# SFX100_LeonardoBreakout.net
KiCad netlist of a schematic drawn in EAGLE
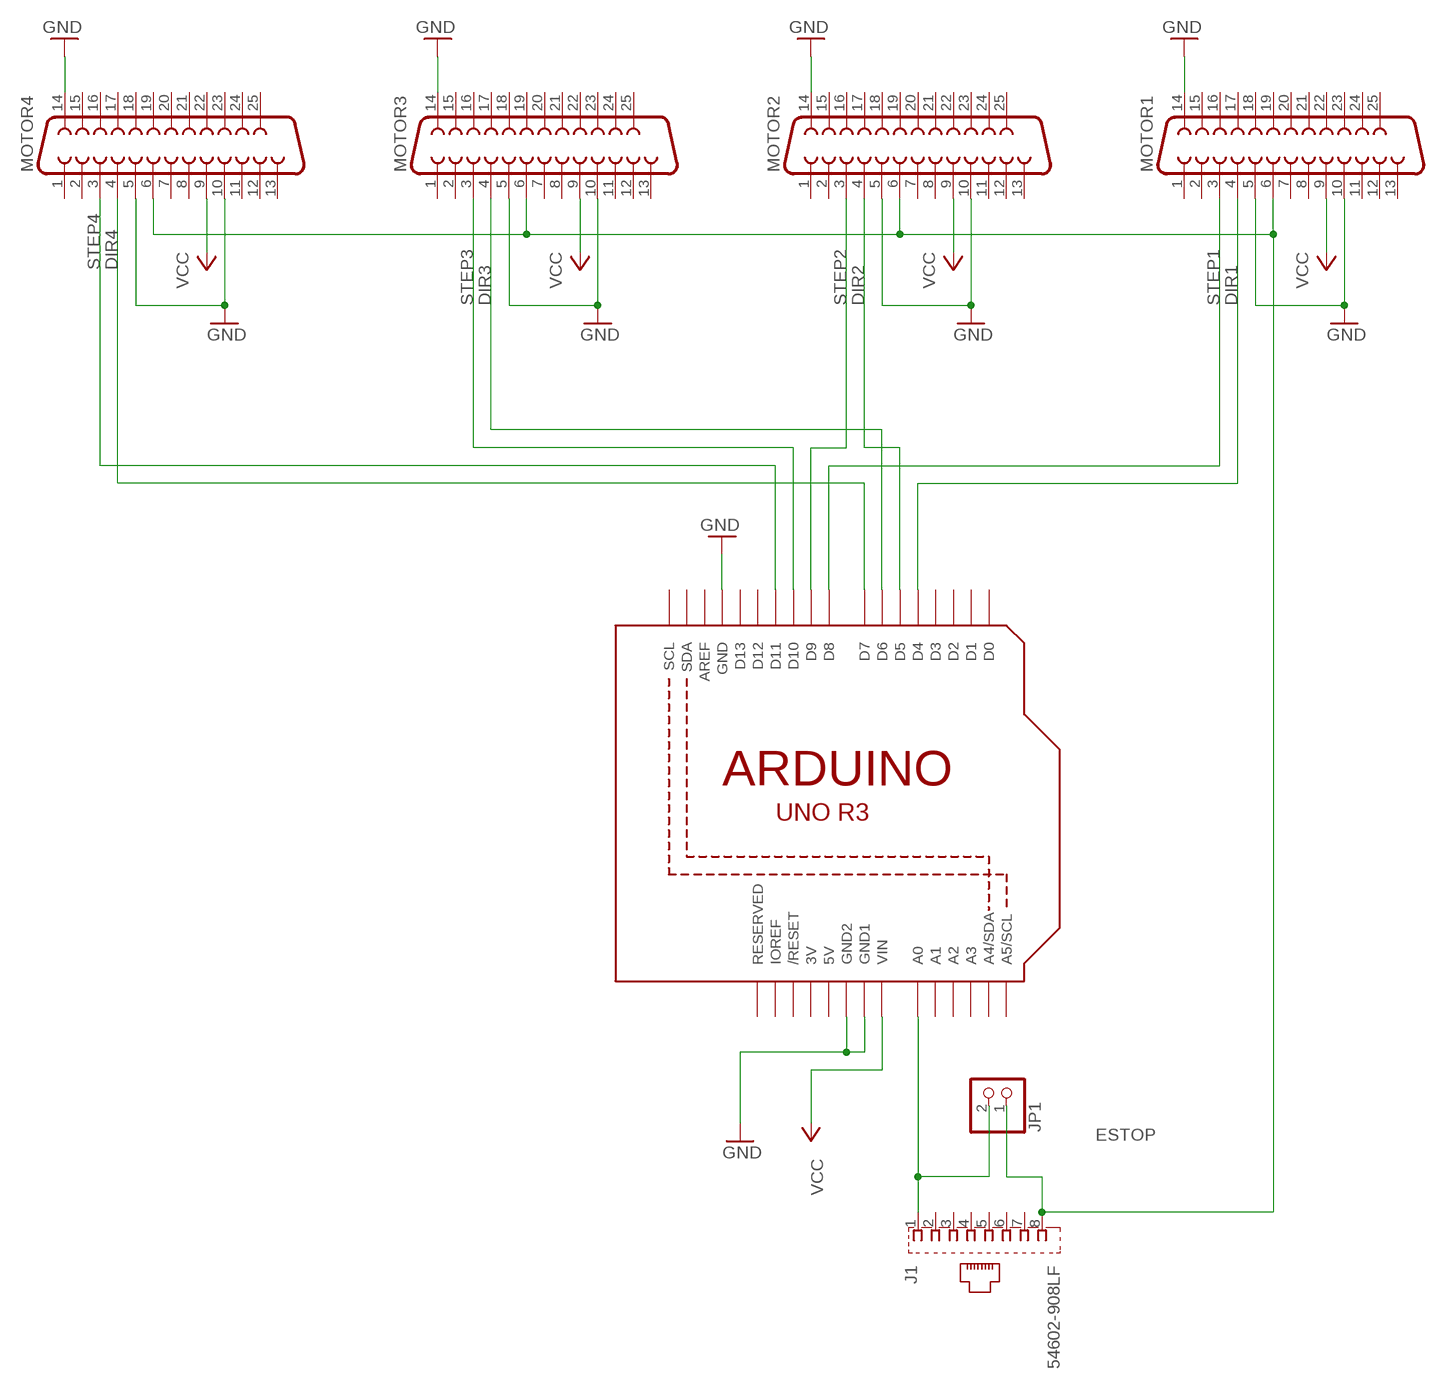
[diagram p0: schematic, sheet 1]

(export (version "E")
  (design (tool "Eeschema 10.0.6"))
  (components
    (comp (ref "J1")
      (value "54602-908LF")
      (footprint "eagle-import:AMPHENOL_54602-908LF")
      (fields (field (name "DIGI-KEY_PART_NUMBER") "609-1046-ND") (field (name "MF") "Amphenol ICC"))
      (libsource (lib "eagle-import") (part "54602-908LF"))
    )
    (comp (ref "JP1")
      (value "PINHD-1X2")
      (footprint "eagle-import:1X02")
      (libsource (lib "eagle-import") (part "PINHD-1X2"))
    )
    (comp (ref "MOTOR1")
      (value "F25V")
      (footprint "eagle-import:F25V")
      (libsource (lib "eagle-import") (part "F25V"))
    )
    (comp (ref "MOTOR2")
      (value "F25V")
      (footprint "eagle-import:F25V")
      (libsource (lib "eagle-import") (part "F25V"))
    )
    (comp (ref "MOTOR3")
      (value "F25V")
      (footprint "eagle-import:F25V")
      (libsource (lib "eagle-import") (part "F25V"))
    )
    (comp (ref "MOTOR4")
      (value "F25V")
      (footprint "eagle-import:F25V")
      (libsource (lib "eagle-import") (part "F25V"))
    )
    (comp (ref "U1")
      (value "ARDUINOR3-BPLACE")
      (footprint "eagle-import:ARDUINOR3-BPLACE")
      (libsource (lib "eagle-import") (part "ARDUINOR3-BPLACE"))
    )
  )
  (nets
    (net (code "1") (name "/3V") (class "Default")
      (node (ref "U1") (pin "3V") (pinfunction "3V_3V") (pintype "power_in"))
    )
    (net (code "2") (name "/5V") (class "Default")
      (node (ref "U1") (pin "5V") (pinfunction "5V_5V") (pintype "power_in"))
    )
    (net (code "3") (name "/DIR1") (class "Default")
      (node (ref "MOTOR1") (pin "4") (pinfunction "4_4") (pintype "passive"))
      (node (ref "U1") (pin "D4") (pinfunction "D4_D4") (pintype "bidirectional"))
    )
    (net (code "4") (name "/DIR2") (class "Default")
      (node (ref "MOTOR2") (pin "4") (pinfunction "4_4") (pintype "passive"))
      (node (ref "U1") (pin "D5") (pinfunction "D5_D5") (pintype "bidirectional"))
    )
    (net (code "5") (name "/DIR3") (class "Default")
      (node (ref "MOTOR3") (pin "4") (pinfunction "4_4") (pintype "passive"))
      (node (ref "U1") (pin "D6") (pinfunction "D6_D6") (pintype "bidirectional"))
    )
    (net (code "6") (name "/DIR4") (class "Default")
      (node (ref "MOTOR4") (pin "4") (pinfunction "4_4") (pintype "passive"))
      (node (ref "U1") (pin "D7") (pinfunction "D7_D7") (pintype "bidirectional"))
    )
    (net (code "7") (name "/ESTOP") (class "Default")
      (node (ref "J1") (pin "8") (pinfunction "8_8") (pintype "passive"))
      (node (ref "JP1") (pin "1") (pinfunction "1_1") (pintype "passive"))
      (node (ref "MOTOR1") (pin "6") (pinfunction "6_6") (pintype "passive"))
      (node (ref "MOTOR2") (pin "6") (pinfunction "6_6") (pintype "passive"))
      (node (ref "MOTOR3") (pin "6") (pinfunction "6_6") (pintype "passive"))
      (node (ref "MOTOR4") (pin "6") (pinfunction "6_6") (pintype "passive"))
    )
    (net (code "8") (name "/STEP1") (class "Default")
      (node (ref "MOTOR1") (pin "3") (pinfunction "3_3") (pintype "passive"))
      (node (ref "U1") (pin "D8") (pinfunction "D8_D8") (pintype "bidirectional"))
    )
    (net (code "9") (name "/STEP2") (class "Default")
      (node (ref "MOTOR2") (pin "3") (pinfunction "3_3") (pintype "passive"))
      (node (ref "U1") (pin "D9") (pinfunction "D9_D9") (pintype "bidirectional"))
    )
    (net (code "10") (name "/STEP3") (class "Default")
      (node (ref "MOTOR3") (pin "3") (pinfunction "3_3") (pintype "passive"))
      (node (ref "U1") (pin "D10") (pinfunction "D10_D10") (pintype "bidirectional"))
    )
    (net (code "11") (name "/STEP4") (class "Default")
      (node (ref "MOTOR4") (pin "3") (pinfunction "3_3") (pintype "passive"))
      (node (ref "U1") (pin "D11") (pinfunction "D11_D11") (pintype "bidirectional"))
    )
    (net (code "12") (name "GND") (class "Default")
      (node (ref "MOTOR1") (pin "10") (pinfunction "10_10") (pintype "passive"))
      (node (ref "MOTOR1") (pin "14") (pinfunction "14_14") (pintype "passive"))
      (node (ref "MOTOR1") (pin "5") (pinfunction "5_5") (pintype "passive"))
      (node (ref "MOTOR2") (pin "10") (pinfunction "10_10") (pintype "passive"))
      (node (ref "MOTOR2") (pin "14") (pinfunction "14_14") (pintype "passive"))
      (node (ref "MOTOR2") (pin "5") (pinfunction "5_5") (pintype "passive"))
      (node (ref "MOTOR3") (pin "10") (pinfunction "10_10") (pintype "passive"))
      (node (ref "MOTOR3") (pin "14") (pinfunction "14_14") (pintype "passive"))
      (node (ref "MOTOR3") (pin "5") (pinfunction "5_5") (pintype "passive"))
      (node (ref "MOTOR4") (pin "10") (pinfunction "10_10") (pintype "passive"))
      (node (ref "MOTOR4") (pin "14") (pinfunction "14_14") (pintype "passive"))
      (node (ref "MOTOR4") (pin "5") (pinfunction "5_5") (pintype "passive"))
      (node (ref "U1") (pin "GND") (pinfunction "GND_GND") (pintype "power_in"))
      (node (ref "U1") (pin "GND1") (pinfunction "GND1_GND1") (pintype "power_in"))
      (node (ref "U1") (pin "GND2") (pinfunction "GND2_GND2") (pintype "power_in"))
    )
    (net (code "13") (name "Net-(J1-Pad1)") (class "Default")
      (node (ref "J1") (pin "1") (pinfunction "1_1") (pintype "passive"))
      (node (ref "JP1") (pin "2") (pinfunction "2_2") (pintype "passive"))
      (node (ref "U1") (pin "A0") (pinfunction "A0_A0") (pintype "bidirectional"))
    )
    (net (code "14") (name "VCC") (class "Default")
      (node (ref "MOTOR1") (pin "9") (pinfunction "9_9") (pintype "passive"))
      (node (ref "MOTOR2") (pin "9") (pinfunction "9_9") (pintype "passive"))
      (node (ref "MOTOR3") (pin "9") (pinfunction "9_9") (pintype "passive"))
      (node (ref "MOTOR4") (pin "9") (pinfunction "9_9") (pintype "passive"))
      (node (ref "U1") (pin "VIN") (pinfunction "VIN_VIN") (pintype "power_in"))
    )
    (net (code "15") (name "unconnected-(J1-Pad2)") (class "Default")
      (node (ref "J1") (pin "2") (pinfunction "2_2") (pintype "passive"))
    )
    (net (code "16") (name "unconnected-(J1-Pad3)") (class "Default")
      (node (ref "J1") (pin "3") (pinfunction "3_3") (pintype "passive"))
    )
    (net (code "17") (name "unconnected-(J1-Pad4)") (class "Default")
      (node (ref "J1") (pin "4") (pinfunction "4_4") (pintype "passive"))
    )
    (net (code "18") (name "unconnected-(J1-Pad5)") (class "Default")
      (node (ref "J1") (pin "5") (pinfunction "5_5") (pintype "passive"))
    )
    (net (code "19") (name "unconnected-(J1-Pad6)") (class "Default")
      (node (ref "J1") (pin "6") (pinfunction "6_6") (pintype "passive"))
    )
    (net (code "20") (name "unconnected-(J1-Pad7)") (class "Default")
      (node (ref "J1") (pin "7") (pinfunction "7_7") (pintype "passive"))
    )
    (net (code "21") (name "unconnected-(MOTOR1-Pad1)") (class "Default")
      (node (ref "MOTOR1") (pin "1") (pinfunction "1_1") (pintype "passive"))
    )
    (net (code "22") (name "unconnected-(MOTOR1-Pad2)") (class "Default")
      (node (ref "MOTOR1") (pin "2") (pinfunction "2_2") (pintype "passive"))
    )
    (net (code "23") (name "unconnected-(MOTOR1-Pad7)") (class "Default")
      (node (ref "MOTOR1") (pin "7") (pinfunction "7_7") (pintype "passive"))
    )
    (net (code "24") (name "unconnected-(MOTOR1-Pad8)") (class "Default")
      (node (ref "MOTOR1") (pin "8") (pinfunction "8_8") (pintype "passive"))
    )
    (net (code "25") (name "unconnected-(MOTOR1-Pad11)") (class "Default")
      (node (ref "MOTOR1") (pin "11") (pinfunction "11_11") (pintype "passive"))
    )
    (net (code "26") (name "unconnected-(MOTOR1-Pad12)") (class "Default")
      (node (ref "MOTOR1") (pin "12") (pinfunction "12_12") (pintype "passive"))
    )
    (net (code "27") (name "unconnected-(MOTOR1-Pad13)") (class "Default")
      (node (ref "MOTOR1") (pin "13") (pinfunction "13_13") (pintype "passive"))
    )
    (net (code "28") (name "unconnected-(MOTOR1-Pad15)") (class "Default")
      (node (ref "MOTOR1") (pin "15") (pinfunction "15_15") (pintype "passive"))
    )
    (net (code "29") (name "unconnected-(MOTOR1-Pad16)") (class "Default")
      (node (ref "MOTOR1") (pin "16") (pinfunction "16_16") (pintype "passive"))
    )
    (net (code "30") (name "unconnected-(MOTOR1-Pad17)") (class "Default")
      (node (ref "MOTOR1") (pin "17") (pinfunction "17_17") (pintype "passive"))
    )
    (net (code "31") (name "unconnected-(MOTOR1-Pad18)") (class "Default")
      (node (ref "MOTOR1") (pin "18") (pinfunction "18_18") (pintype "passive"))
    )
    (net (code "32") (name "unconnected-(MOTOR1-Pad19)") (class "Default")
      (node (ref "MOTOR1") (pin "19") (pinfunction "19_19") (pintype "passive"))
    )
    (net (code "33") (name "unconnected-(MOTOR1-Pad20)") (class "Default")
      (node (ref "MOTOR1") (pin "20") (pinfunction "20_20") (pintype "passive"))
    )
    (net (code "34") (name "unconnected-(MOTOR1-Pad21)") (class "Default")
      (node (ref "MOTOR1") (pin "21") (pinfunction "21_21") (pintype "passive"))
    )
    (net (code "35") (name "unconnected-(MOTOR1-Pad22)") (class "Default")
      (node (ref "MOTOR1") (pin "22") (pinfunction "22_22") (pintype "passive"))
    )
    (net (code "36") (name "unconnected-(MOTOR1-Pad23)") (class "Default")
      (node (ref "MOTOR1") (pin "23") (pinfunction "23_23") (pintype "passive"))
    )
    (net (code "37") (name "unconnected-(MOTOR1-Pad24)") (class "Default")
      (node (ref "MOTOR1") (pin "24") (pinfunction "24_24") (pintype "passive"))
    )
    (net (code "38") (name "unconnected-(MOTOR1-Pad25)") (class "Default")
      (node (ref "MOTOR1") (pin "25") (pinfunction "25_25") (pintype "passive"))
    )
    (net (code "39") (name "unconnected-(MOTOR2-Pad1)") (class "Default")
      (node (ref "MOTOR2") (pin "1") (pinfunction "1_1") (pintype "passive"))
    )
    (net (code "40") (name "unconnected-(MOTOR2-Pad2)") (class "Default")
      (node (ref "MOTOR2") (pin "2") (pinfunction "2_2") (pintype "passive"))
    )
    (net (code "41") (name "unconnected-(MOTOR2-Pad7)") (class "Default")
      (node (ref "MOTOR2") (pin "7") (pinfunction "7_7") (pintype "passive"))
    )
    (net (code "42") (name "unconnected-(MOTOR2-Pad8)") (class "Default")
      (node (ref "MOTOR2") (pin "8") (pinfunction "8_8") (pintype "passive"))
    )
    (net (code "43") (name "unconnected-(MOTOR2-Pad11)") (class "Default")
      (node (ref "MOTOR2") (pin "11") (pinfunction "11_11") (pintype "passive"))
    )
    (net (code "44") (name "unconnected-(MOTOR2-Pad12)") (class "Default")
      (node (ref "MOTOR2") (pin "12") (pinfunction "12_12") (pintype "passive"))
    )
    (net (code "45") (name "unconnected-(MOTOR2-Pad13)") (class "Default")
      (node (ref "MOTOR2") (pin "13") (pinfunction "13_13") (pintype "passive"))
    )
    (net (code "46") (name "unconnected-(MOTOR2-Pad15)") (class "Default")
      (node (ref "MOTOR2") (pin "15") (pinfunction "15_15") (pintype "passive"))
    )
    (net (code "47") (name "unconnected-(MOTOR2-Pad16)") (class "Default")
      (node (ref "MOTOR2") (pin "16") (pinfunction "16_16") (pintype "passive"))
    )
    (net (code "48") (name "unconnected-(MOTOR2-Pad17)") (class "Default")
      (node (ref "MOTOR2") (pin "17") (pinfunction "17_17") (pintype "passive"))
    )
    (net (code "49") (name "unconnected-(MOTOR2-Pad18)") (class "Default")
      (node (ref "MOTOR2") (pin "18") (pinfunction "18_18") (pintype "passive"))
    )
    (net (code "50") (name "unconnected-(MOTOR2-Pad19)") (class "Default")
      (node (ref "MOTOR2") (pin "19") (pinfunction "19_19") (pintype "passive"))
    )
    (net (code "51") (name "unconnected-(MOTOR2-Pad20)") (class "Default")
      (node (ref "MOTOR2") (pin "20") (pinfunction "20_20") (pintype "passive"))
    )
    (net (code "52") (name "unconnected-(MOTOR2-Pad21)") (class "Default")
      (node (ref "MOTOR2") (pin "21") (pinfunction "21_21") (pintype "passive"))
    )
    (net (code "53") (name "unconnected-(MOTOR2-Pad22)") (class "Default")
      (node (ref "MOTOR2") (pin "22") (pinfunction "22_22") (pintype "passive"))
    )
    (net (code "54") (name "unconnected-(MOTOR2-Pad23)") (class "Default")
      (node (ref "MOTOR2") (pin "23") (pinfunction "23_23") (pintype "passive"))
    )
    (net (code "55") (name "unconnected-(MOTOR2-Pad24)") (class "Default")
      (node (ref "MOTOR2") (pin "24") (pinfunction "24_24") (pintype "passive"))
    )
    (net (code "56") (name "unconnected-(MOTOR2-Pad25)") (class "Default")
      (node (ref "MOTOR2") (pin "25") (pinfunction "25_25") (pintype "passive"))
    )
    (net (code "57") (name "unconnected-(MOTOR3-Pad1)") (class "Default")
      (node (ref "MOTOR3") (pin "1") (pinfunction "1_1") (pintype "passive"))
    )
    (net (code "58") (name "unconnected-(MOTOR3-Pad2)") (class "Default")
      (node (ref "MOTOR3") (pin "2") (pinfunction "2_2") (pintype "passive"))
    )
    (net (code "59") (name "unconnected-(MOTOR3-Pad7)") (class "Default")
      (node (ref "MOTOR3") (pin "7") (pinfunction "7_7") (pintype "passive"))
    )
    (net (code "60") (name "unconnected-(MOTOR3-Pad8)") (class "Default")
      (node (ref "MOTOR3") (pin "8") (pinfunction "8_8") (pintype "passive"))
    )
    (net (code "61") (name "unconnected-(MOTOR3-Pad11)") (class "Default")
      (node (ref "MOTOR3") (pin "11") (pinfunction "11_11") (pintype "passive"))
    )
    (net (code "62") (name "unconnected-(MOTOR3-Pad12)") (class "Default")
      (node (ref "MOTOR3") (pin "12") (pinfunction "12_12") (pintype "passive"))
    )
    (net (code "63") (name "unconnected-(MOTOR3-Pad13)") (class "Default")
      (node (ref "MOTOR3") (pin "13") (pinfunction "13_13") (pintype "passive"))
    )
    (net (code "64") (name "unconnected-(MOTOR3-Pad15)") (class "Default")
      (node (ref "MOTOR3") (pin "15") (pinfunction "15_15") (pintype "passive"))
    )
    (net (code "65") (name "unconnected-(MOTOR3-Pad16)") (class "Default")
      (node (ref "MOTOR3") (pin "16") (pinfunction "16_16") (pintype "passive"))
    )
    (net (code "66") (name "unconnected-(MOTOR3-Pad17)") (class "Default")
      (node (ref "MOTOR3") (pin "17") (pinfunction "17_17") (pintype "passive"))
    )
    (net (code "67") (name "unconnected-(MOTOR3-Pad18)") (class "Default")
      (node (ref "MOTOR3") (pin "18") (pinfunction "18_18") (pintype "passive"))
    )
    (net (code "68") (name "unconnected-(MOTOR3-Pad19)") (class "Default")
      (node (ref "MOTOR3") (pin "19") (pinfunction "19_19") (pintype "passive"))
    )
    (net (code "69") (name "unconnected-(MOTOR3-Pad20)") (class "Default")
      (node (ref "MOTOR3") (pin "20") (pinfunction "20_20") (pintype "passive"))
    )
    (net (code "70") (name "unconnected-(MOTOR3-Pad21)") (class "Default")
      (node (ref "MOTOR3") (pin "21") (pinfunction "21_21") (pintype "passive"))
    )
    (net (code "71") (name "unconnected-(MOTOR3-Pad22)") (class "Default")
      (node (ref "MOTOR3") (pin "22") (pinfunction "22_22") (pintype "passive"))
    )
    (net (code "72") (name "unconnected-(MOTOR3-Pad23)") (class "Default")
      (node (ref "MOTOR3") (pin "23") (pinfunction "23_23") (pintype "passive"))
    )
    (net (code "73") (name "unconnected-(MOTOR3-Pad24)") (class "Default")
      (node (ref "MOTOR3") (pin "24") (pinfunction "24_24") (pintype "passive"))
    )
    (net (code "74") (name "unconnected-(MOTOR3-Pad25)") (class "Default")
      (node (ref "MOTOR3") (pin "25") (pinfunction "25_25") (pintype "passive"))
    )
    (net (code "75") (name "unconnected-(MOTOR4-Pad1)") (class "Default")
      (node (ref "MOTOR4") (pin "1") (pinfunction "1_1") (pintype "passive"))
    )
    (net (code "76") (name "unconnected-(MOTOR4-Pad2)") (class "Default")
      (node (ref "MOTOR4") (pin "2") (pinfunction "2_2") (pintype "passive"))
    )
    (net (code "77") (name "unconnected-(MOTOR4-Pad7)") (class "Default")
      (node (ref "MOTOR4") (pin "7") (pinfunction "7_7") (pintype "passive"))
    )
    (net (code "78") (name "unconnected-(MOTOR4-Pad8)") (class "Default")
      (node (ref "MOTOR4") (pin "8") (pinfunction "8_8") (pintype "passive"))
    )
    (net (code "79") (name "unconnected-(MOTOR4-Pad11)") (class "Default")
      (node (ref "MOTOR4") (pin "11") (pinfunction "11_11") (pintype "passive"))
    )
    (net (code "80") (name "unconnected-(MOTOR4-Pad12)") (class "Default")
      (node (ref "MOTOR4") (pin "12") (pinfunction "12_12") (pintype "passive"))
    )
    (net (code "81") (name "unconnected-(MOTOR4-Pad13)") (class "Default")
      (node (ref "MOTOR4") (pin "13") (pinfunction "13_13") (pintype "passive"))
    )
    (net (code "82") (name "unconnected-(MOTOR4-Pad15)") (class "Default")
      (node (ref "MOTOR4") (pin "15") (pinfunction "15_15") (pintype "passive"))
    )
    (net (code "83") (name "unconnected-(MOTOR4-Pad16)") (class "Default")
      (node (ref "MOTOR4") (pin "16") (pinfunction "16_16") (pintype "passive"))
    )
    (net (code "84") (name "unconnected-(MOTOR4-Pad17)") (class "Default")
      (node (ref "MOTOR4") (pin "17") (pinfunction "17_17") (pintype "passive"))
    )
    (net (code "85") (name "unconnected-(MOTOR4-Pad18)") (class "Default")
      (node (ref "MOTOR4") (pin "18") (pinfunction "18_18") (pintype "passive"))
    )
    (net (code "86") (name "unconnected-(MOTOR4-Pad19)") (class "Default")
      (node (ref "MOTOR4") (pin "19") (pinfunction "19_19") (pintype "passive"))
    )
    (net (code "87") (name "unconnected-(MOTOR4-Pad20)") (class "Default")
      (node (ref "MOTOR4") (pin "20") (pinfunction "20_20") (pintype "passive"))
    )
    (net (code "88") (name "unconnected-(MOTOR4-Pad21)") (class "Default")
      (node (ref "MOTOR4") (pin "21") (pinfunction "21_21") (pintype "passive"))
    )
    (net (code "89") (name "unconnected-(MOTOR4-Pad22)") (class "Default")
      (node (ref "MOTOR4") (pin "22") (pinfunction "22_22") (pintype "passive"))
    )
    (net (code "90") (name "unconnected-(MOTOR4-Pad23)") (class "Default")
      (node (ref "MOTOR4") (pin "23") (pinfunction "23_23") (pintype "passive"))
    )
    (net (code "91") (name "unconnected-(MOTOR4-Pad24)") (class "Default")
      (node (ref "MOTOR4") (pin "24") (pinfunction "24_24") (pintype "passive"))
    )
    (net (code "92") (name "unconnected-(MOTOR4-Pad25)") (class "Default")
      (node (ref "MOTOR4") (pin "25") (pinfunction "25_25") (pintype "passive"))
    )
    (net (code "93") (name "unconnected-(U1-A4{slash}SDA-PadA4)") (class "Default")
      (node (ref "U1") (pin "A4") (pinfunction "A4/SDA_A4") (pintype "bidirectional"))
    )
    (net (code "94") (name "unconnected-(U1-A5{slash}SCL-PadA5)") (class "Default")
      (node (ref "U1") (pin "A5") (pinfunction "A5/SCL_A5") (pintype "bidirectional"))
    )
    (net (code "95") (name "unconnected-(U1-PadA1)") (class "Default")
      (node (ref "U1") (pin "A1") (pinfunction "A1_A1") (pintype "bidirectional"))
    )
    (net (code "96") (name "unconnected-(U1-PadA2)") (class "Default")
      (node (ref "U1") (pin "A2") (pinfunction "A2_A2") (pintype "bidirectional"))
    )
    (net (code "97") (name "unconnected-(U1-PadA3)") (class "Default")
      (node (ref "U1") (pin "A3") (pinfunction "A3_A3") (pintype "bidirectional"))
    )
    (net (code "98") (name "unconnected-(U1-PadAREF)") (class "Default")
      (node (ref "U1") (pin "AREF") (pinfunction "AREF_AREF") (pintype "bidirectional"))
    )
    (net (code "99") (name "unconnected-(U1-PadD0)") (class "Default")
      (node (ref "U1") (pin "D0") (pinfunction "D0_D0") (pintype "bidirectional"))
    )
    (net (code "100") (name "unconnected-(U1-PadD1)") (class "Default")
      (node (ref "U1") (pin "D1") (pinfunction "D1_D1") (pintype "bidirectional"))
    )
    (net (code "101") (name "unconnected-(U1-PadD2)") (class "Default")
      (node (ref "U1") (pin "D2") (pinfunction "D2_D2") (pintype "bidirectional"))
    )
    (net (code "102") (name "unconnected-(U1-PadD3)") (class "Default")
      (node (ref "U1") (pin "D3") (pinfunction "D3_D3") (pintype "bidirectional"))
    )
    (net (code "103") (name "unconnected-(U1-PadD12)") (class "Default")
      (node (ref "U1") (pin "D12") (pinfunction "D12_D12") (pintype "bidirectional"))
    )
    (net (code "104") (name "unconnected-(U1-PadD13)") (class "Default")
      (node (ref "U1") (pin "D13") (pinfunction "D13_D13") (pintype "bidirectional"))
    )
    (net (code "105") (name "unconnected-(U1-PadIOREF)") (class "Default")
      (node (ref "U1") (pin "IOREF") (pinfunction "IOREF_IOREF") (pintype "output"))
    )
    (net (code "106") (name "unconnected-(U1-PadRESERVED)") (class "Default")
      (node (ref "U1") (pin "RESERVED") (pinfunction "RESERVED_RESERVED") (pintype "no_connect"))
    )
    (net (code "107") (name "unconnected-(U1-PadSCL)") (class "Default")
      (node (ref "U1") (pin "SCL") (pinfunction "SCL_SCL") (pintype "bidirectional"))
    )
    (net (code "108") (name "unconnected-(U1-PadSDA)") (class "Default")
      (node (ref "U1") (pin "SDA") (pinfunction "SDA_SDA") (pintype "bidirectional"))
    )
    (net (code "109") (name "unconnected-(U1-{slash}RESET-PadRESET)") (class "Default")
      (node (ref "U1") (pin "RESET") (pinfunction "/RESET_RESET") (pintype "bidirectional"))
    )
  )
)
